# SCH_New-Project_2026-02-03.net
KiCad netlist of a schematic drawn in EasyEDA
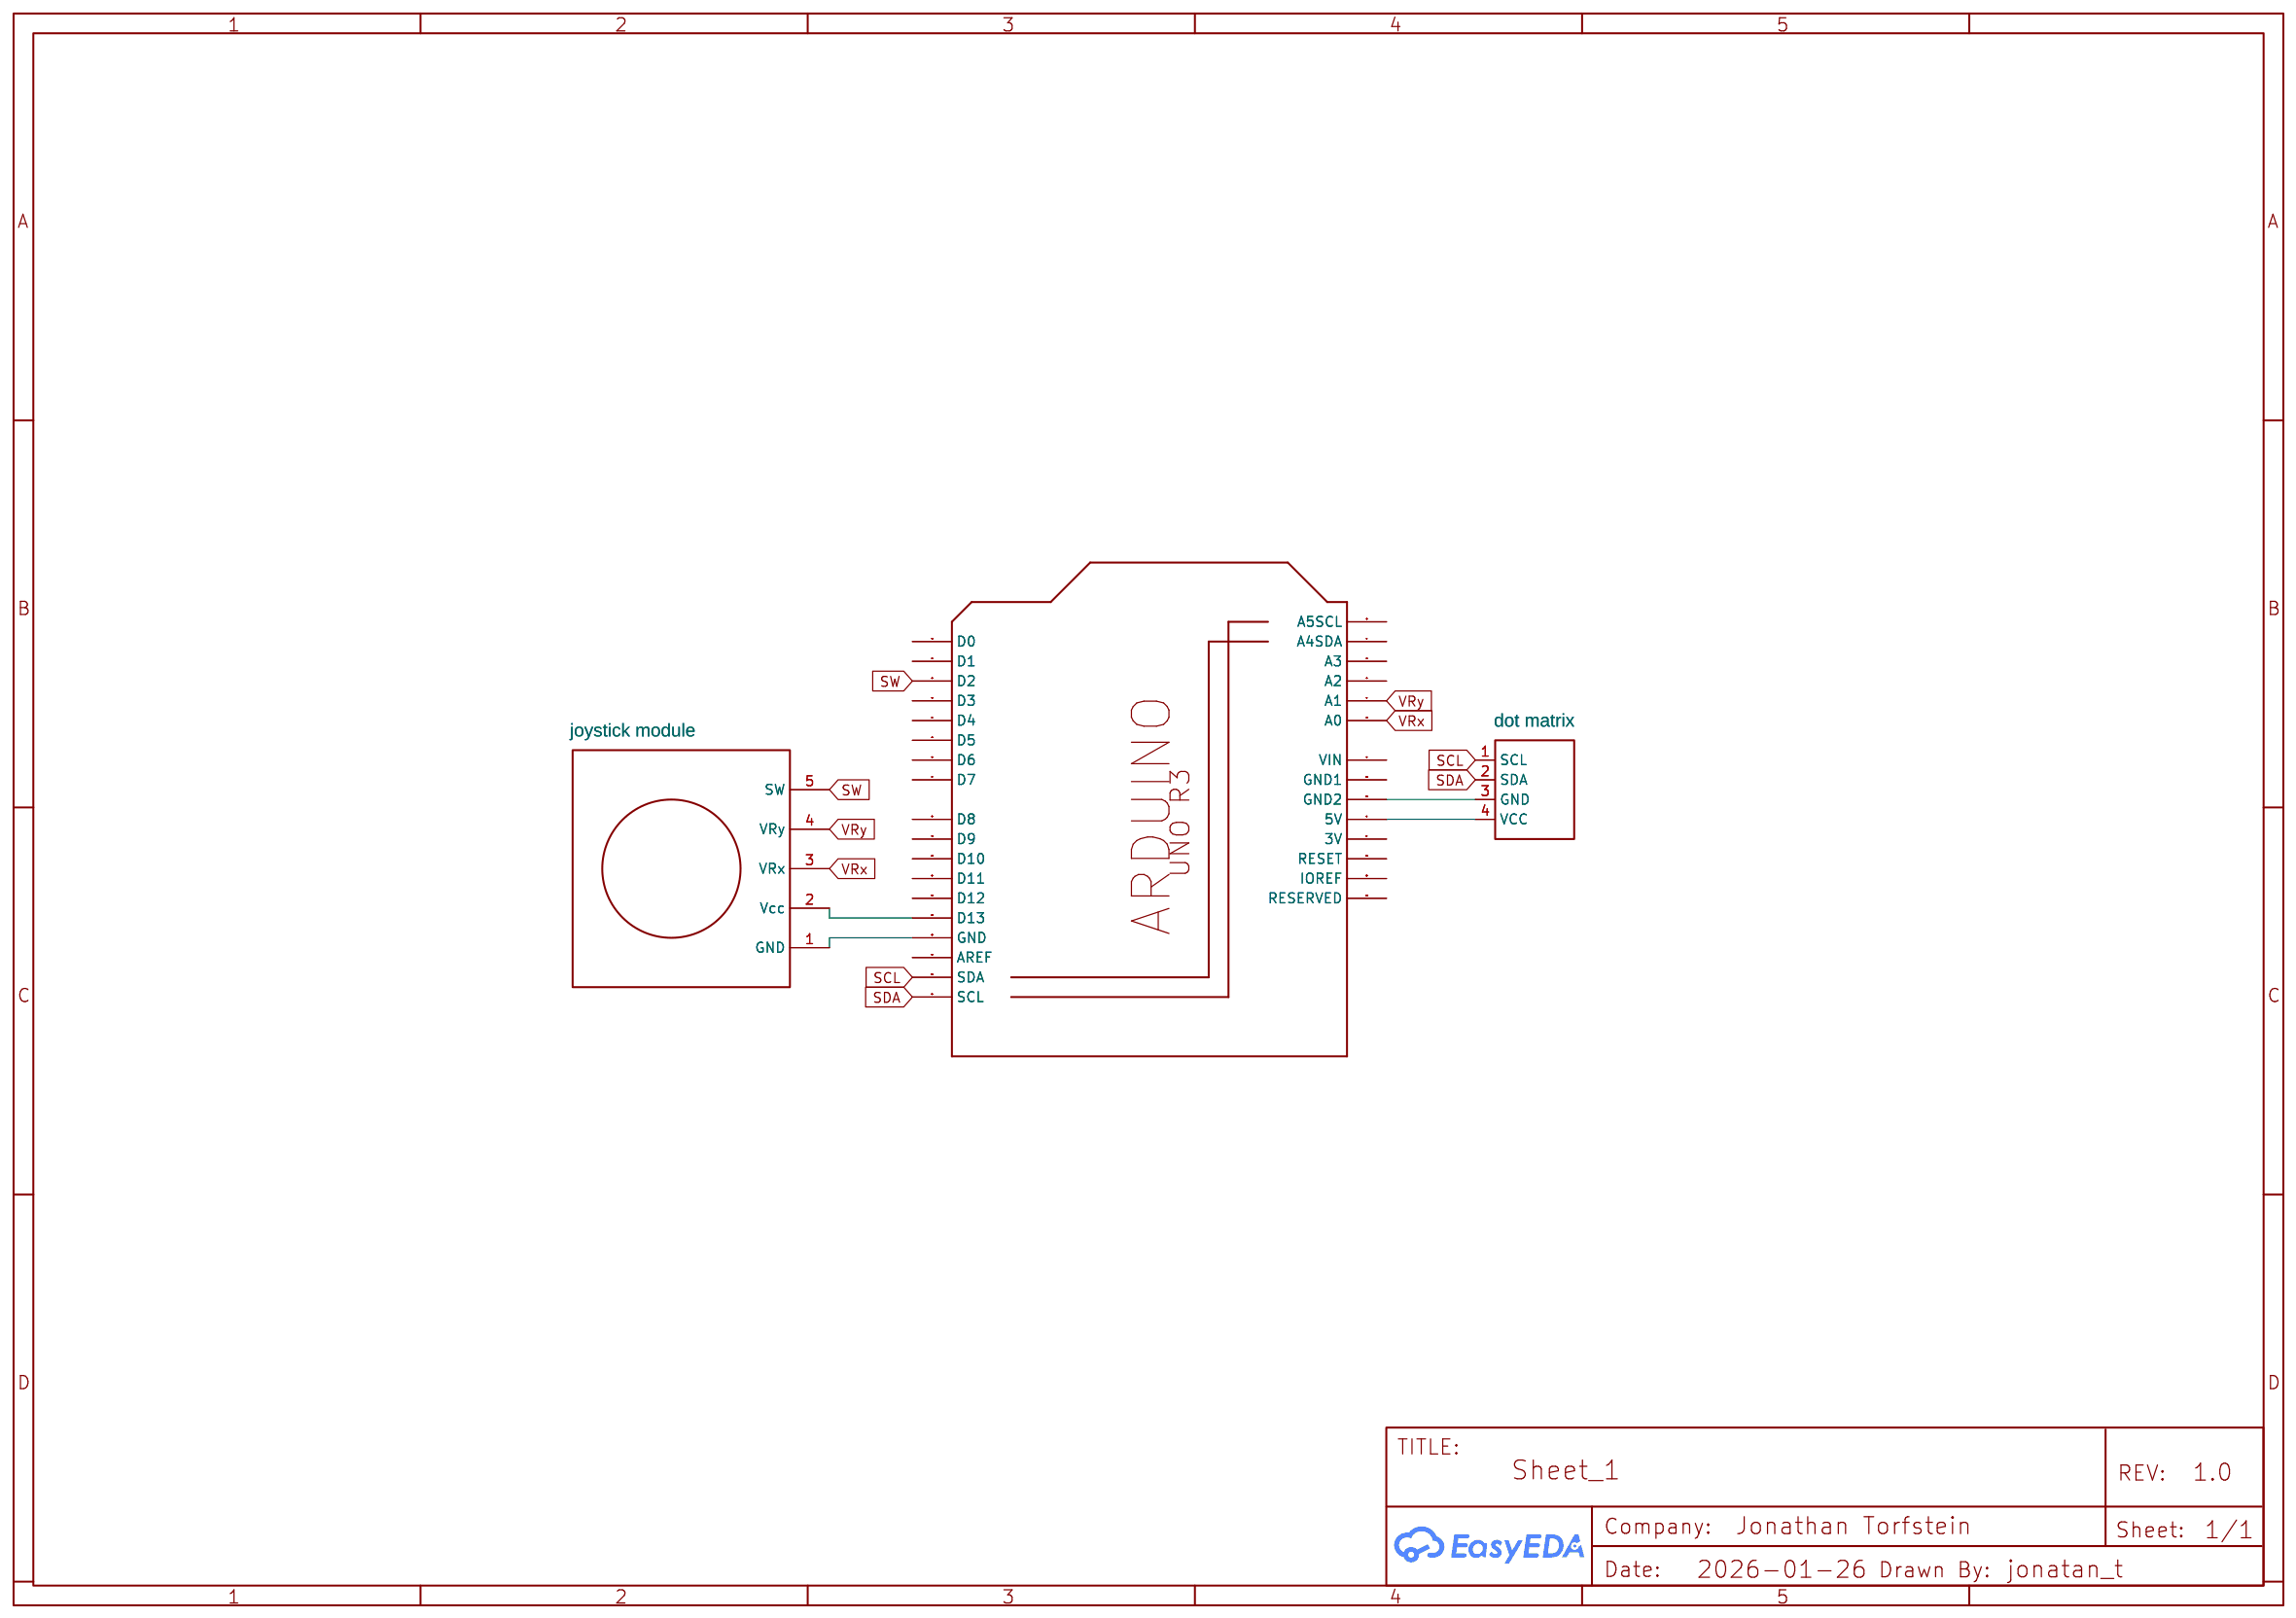
[diagram p0: schematic sheet]

(export (version "E")
  (design (tool "Eeschema 10.0.6"))
  (components
    (comp (ref "U1") (value "ARDUINOR3-DIMENSION") (libsource (lib "") (part "ARDUINOR3-DIMENSION")))
    (comp (ref "U2")
      (value "dot matrix")
      (fields
        (field (name "Manufacturer Part") "350424-1")
        (field (name "Manufacturer") "TE Connectivity(泰科电子)")
      )
      (libsource (lib "") (part "350424-1"))
    )
    (comp (ref "U3") (value "joystick module") (libsource (lib "") (part "HW-504JOYSTICK")))
  )
  (nets
    (net (code "1") (name "Net-(U2-GND)") (class "Default")
      (node (ref "U1") (pin "GND2") (pinfunction "GND2_GND2") (pintype "passive"))
      (node (ref "U2") (pin "3") (pinfunction "GND_3") (pintype "unspecified"))
    )
    (net (code "2") (name "Net-(U2-VCC)") (class "Default")
      (node (ref "U1") (pin "5V") (pinfunction "5V_5V") (pintype "passive"))
      (node (ref "U2") (pin "4") (pinfunction "VCC_4") (pintype "unspecified"))
    )
    (net (code "3") (name "Net-(U3-GND)") (class "Default")
      (node (ref "U1") (pin "GND") (pinfunction "GND_GND") (pintype "passive"))
      (node (ref "U3") (pin "1") (pinfunction "GND_1") (pintype "unspecified"))
    )
    (net (code "4") (name "Net-(U3-Vcc)") (class "Default")
      (node (ref "U1") (pin "D13") (pinfunction "D13_D13") (pintype "unspecified"))
      (node (ref "U3") (pin "2") (pinfunction "Vcc_2") (pintype "unspecified"))
    )
    (net (code "5") (name "SCL") (class "Default")
      (node (ref "U1") (pin "SDA") (pinfunction "SDA_SDA") (pintype "unspecified"))
      (node (ref "U2") (pin "1") (pinfunction "SCL_1") (pintype "unspecified"))
    )
    (net (code "6") (name "SDA") (class "Default")
      (node (ref "U1") (pin "SCL") (pinfunction "SCL_SCL") (pintype "unspecified"))
      (node (ref "U2") (pin "2") (pinfunction "SDA_2") (pintype "unspecified"))
    )
    (net (code "7") (name "SW") (class "Default")
      (node (ref "U1") (pin "D2") (pinfunction "D2_D2") (pintype "unspecified"))
      (node (ref "U3") (pin "5") (pinfunction "SW_5") (pintype "unspecified"))
    )
    (net (code "8") (name "VRx") (class "Default")
      (node (ref "U1") (pin "A0") (pinfunction "A0_A0") (pintype "unspecified"))
      (node (ref "U3") (pin "3") (pinfunction "VRx_3") (pintype "unspecified"))
    )
    (net (code "9") (name "VRy") (class "Default")
      (node (ref "U1") (pin "A1") (pinfunction "A1_A1") (pintype "unspecified"))
      (node (ref "U3") (pin "4") (pinfunction "VRy_4") (pintype "unspecified"))
    )
    (net (code "10") (name "unconnected-(U1-A4SDA-PadA4)") (class "Default")
      (node (ref "U1") (pin "A4") (pinfunction "A4SDA_A4") (pintype "unspecified"))
    )
    (net (code "11") (name "unconnected-(U1-A5SCL-PadA5)") (class "Default")
      (node (ref "U1") (pin "A5") (pinfunction "A5SCL_A5") (pintype "unspecified"))
    )
    (net (code "12") (name "unconnected-(U1-Pad3V)") (class "Default")
      (node (ref "U1") (pin "3V") (pinfunction "3V_3V") (pintype "passive"))
    )
    (net (code "13") (name "unconnected-(U1-PadA2)") (class "Default")
      (node (ref "U1") (pin "A2") (pinfunction "A2_A2") (pintype "unspecified"))
    )
    (net (code "14") (name "unconnected-(U1-PadA3)") (class "Default")
      (node (ref "U1") (pin "A3") (pinfunction "A3_A3") (pintype "unspecified"))
    )
    (net (code "15") (name "unconnected-(U1-PadAREF)") (class "Default")
      (node (ref "U1") (pin "AREF") (pinfunction "AREF_AREF") (pintype "unspecified"))
    )
    (net (code "16") (name "unconnected-(U1-PadD0)") (class "Default")
      (node (ref "U1") (pin "D0") (pinfunction "D0_D0") (pintype "unspecified"))
    )
    (net (code "17") (name "unconnected-(U1-PadD1)") (class "Default")
      (node (ref "U1") (pin "D1") (pinfunction "D1_D1") (pintype "unspecified"))
    )
    (net (code "18") (name "unconnected-(U1-PadD3)") (class "Default")
      (node (ref "U1") (pin "D3") (pinfunction "D3_D3") (pintype "unspecified"))
    )
    (net (code "19") (name "unconnected-(U1-PadD4)") (class "Default")
      (node (ref "U1") (pin "D4") (pinfunction "D4_D4") (pintype "unspecified"))
    )
    (net (code "20") (name "unconnected-(U1-PadD5)") (class "Default")
      (node (ref "U1") (pin "D5") (pinfunction "D5_D5") (pintype "unspecified"))
    )
    (net (code "21") (name "unconnected-(U1-PadD6)") (class "Default")
      (node (ref "U1") (pin "D6") (pinfunction "D6_D6") (pintype "unspecified"))
    )
    (net (code "22") (name "unconnected-(U1-PadD7)") (class "Default")
      (node (ref "U1") (pin "D7") (pinfunction "D7_D7") (pintype "unspecified"))
    )
    (net (code "23") (name "unconnected-(U1-PadD8)") (class "Default")
      (node (ref "U1") (pin "D8") (pinfunction "D8_D8") (pintype "unspecified"))
    )
    (net (code "24") (name "unconnected-(U1-PadD9)") (class "Default")
      (node (ref "U1") (pin "D9") (pinfunction "D9_D9") (pintype "unspecified"))
    )
    (net (code "25") (name "unconnected-(U1-PadD10)") (class "Default")
      (node (ref "U1") (pin "D10") (pinfunction "D10_D10") (pintype "unspecified"))
    )
    (net (code "26") (name "unconnected-(U1-PadD11)") (class "Default")
      (node (ref "U1") (pin "D11") (pinfunction "D11_D11") (pintype "unspecified"))
    )
    (net (code "27") (name "unconnected-(U1-PadD12)") (class "Default")
      (node (ref "U1") (pin "D12") (pinfunction "D12_D12") (pintype "unspecified"))
    )
    (net (code "28") (name "unconnected-(U1-PadGND1)") (class "Default")
      (node (ref "U1") (pin "GND1") (pinfunction "GND1_GND1") (pintype "passive"))
    )
    (net (code "29") (name "unconnected-(U1-PadIOREF)") (class "Default")
      (node (ref "U1") (pin "IOREF") (pinfunction "IOREF_IOREF") (pintype "output"))
    )
    (net (code "30") (name "unconnected-(U1-PadRESERVED)") (class "Default")
      (node (ref "U1") (pin "RESERVED") (pinfunction "RESERVED_RESERVED") (pintype "unspecified"))
    )
    (net (code "31") (name "unconnected-(U1-PadRESET)") (class "Default")
      (node (ref "U1") (pin "RESET") (pinfunction "RESET_RESET") (pintype "unspecified"))
    )
    (net (code "32") (name "unconnected-(U1-PadVIN)") (class "Default")
      (node (ref "U1") (pin "VIN") (pinfunction "VIN_VIN") (pintype "passive"))
    )
  )
)
